# Power_Supply_TPS54260.net
KiCad netlist of a schematic drawn in Altium Designer
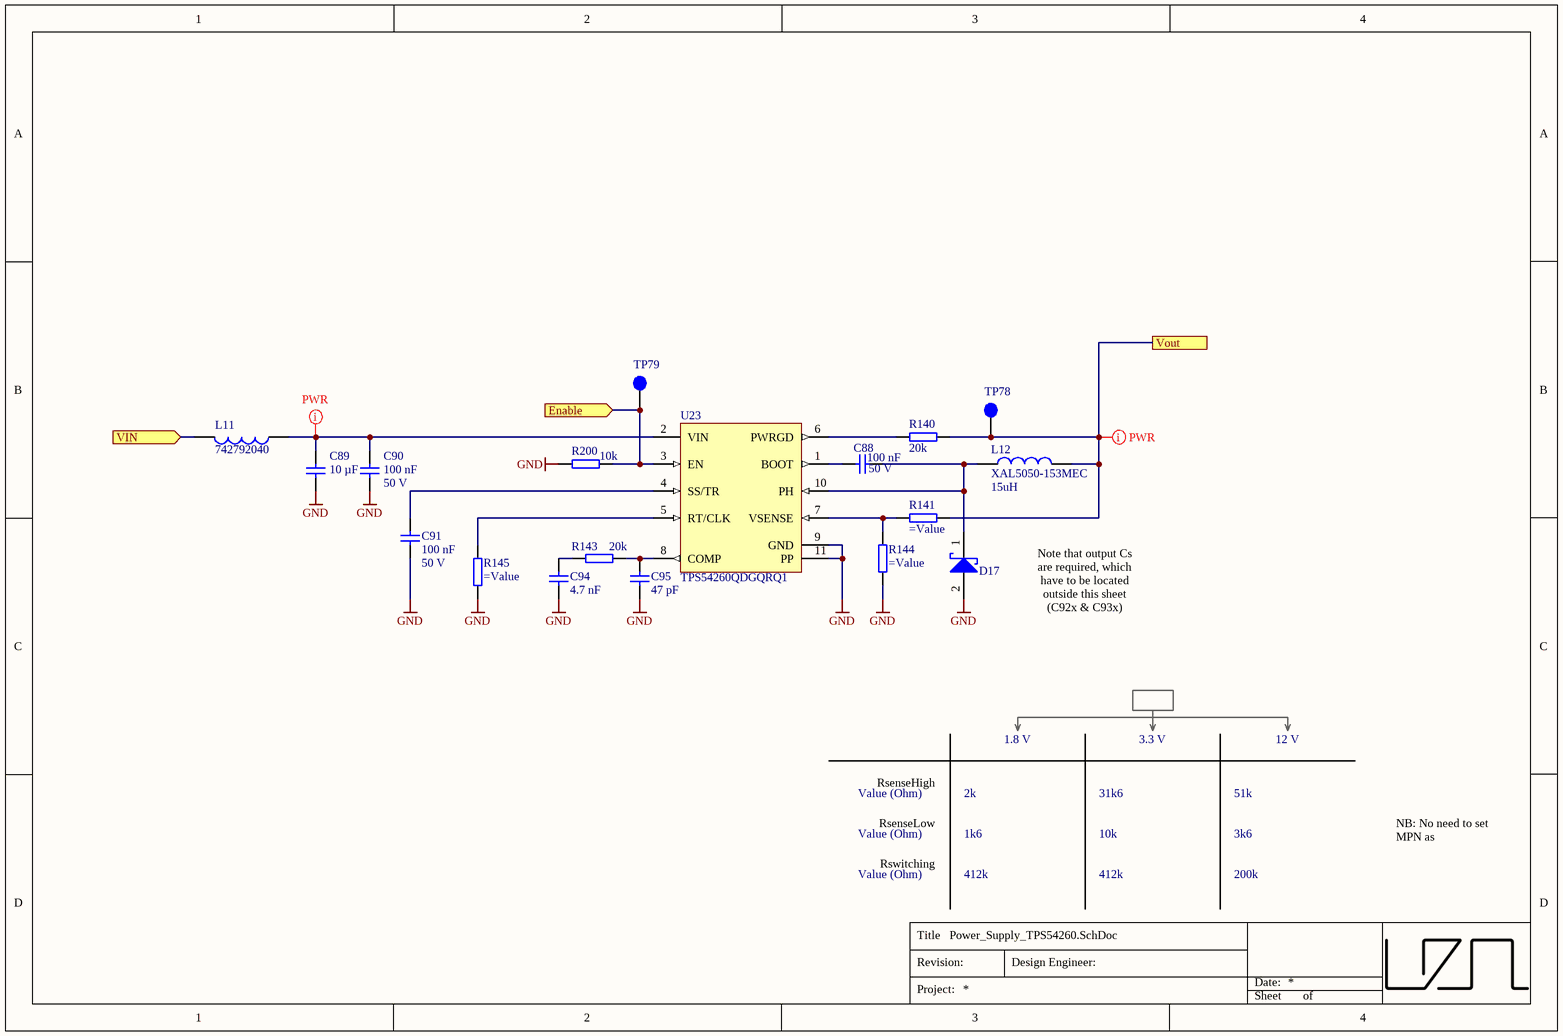
[diagram p0: Power_Supply_TPS54260.SchDoc]

(export (version "E")
  (design (tool "Eeschema 10.0.6"))
  (components
    (comp (ref "C88")
      (value "100 nF")
      (footprint "C_0603_TE")
      (description "Generic capacitor")
      (fields
        (field (name "TOLERANCE") "10 %")
        (field (name "VOLTAGE") "50 V")
        (field (name "MANUFACTURER PART NUMBER") "UZgen_C_0603_100nF_50V_X7R")
        (field (name "CREATED FROM") "AGeiger")
      )
      (libsource (lib "user") (part "CAP-NP"))
    )
    (comp (ref "C89")
      (value "10 µF")
      (footprint "C_1206_TE")
      (description "Generic capacitor")
      (fields
        (field (name "TOLERANCE") "10 %")
        (field (name "MANUFACTURER PART NUMBER") "UZgen_C_1206_10uF_50V_X7R")
        (field (name "CREATED FROM") "MGeier")
      )
      (libsource (lib "user") (part "CAP-NP"))
    )
    (comp (ref "C90")
      (value "100 nF")
      (footprint "C_0603_TE")
      (description "Generic capacitor")
      (fields
        (field (name "TOLERANCE") "10 %")
        (field (name "VOLTAGE") "50 V")
        (field (name "MANUFACTURER PART NUMBER") "UZgen_C_0603_100nF_50V_X7R")
        (field (name "CREATED FROM") "AGeiger")
      )
      (libsource (lib "user") (part "CAP-NP"))
    )
    (comp (ref "C91")
      (value "100 nF")
      (footprint "C_0603_TE")
      (description "Generic capacitor")
      (fields
        (field (name "TOLERANCE") "10 %")
        (field (name "VOLTAGE") "50 V")
        (field (name "MANUFACTURER PART NUMBER") "UZgen_C_0603_100nF_50V_X7R")
        (field (name "CREATED FROM") "AGeiger")
      )
      (libsource (lib "user") (part "CAP-NP"))
    )
    (comp (ref "C94")
      (value "4.7 nF")
      (footprint "C_0603_TE")
      (description "50V 4.7nF C0G ±5% 0603 Multilayer Ceramic Capacitors MLCC")
      (fields
        (field (name "TOLERANCE") "5%")
        (field (name "MANUFACTURER PART NUMBER") "GRM1885C1H472JA01D")
        (field (name "CREATED FROM") "MGeier")
      )
      (libsource (lib "user") (part "CAP-NP"))
    )
    (comp (ref "C95")
      (value "47 pF")
      (footprint "C_0603_TE")
      (description "50V 47pF C0G ±5% 0603 Multilayer Ceramic Capacitors MLCC")
      (fields
        (field (name "TOLERANCE") "5%")
        (field (name "MANUFACTURER PART NUMBER") "CL10C470JB8NNNC")
        (field (name "CREATED FROM") "MGeier")
      )
      (libsource (lib "user") (part "CAP-NP"))
    )
    (comp (ref "D17")
      (value "STPS340UY")
      (footprint "SMB")
      (description "Power Schottky Rectifier, 3 A, 40 V, 0.57 µF")
      (fields
        (field (name "MANUFACTURER") "STMicroelectronics")
        (field (name "LCSC PART NUMBER") "C283520")
        (field (name "CREATED FROM") "MGremer")
      )
      (libsource (lib "user") (part "STPS340-Y"))
    )
    (comp (ref "L11")
      (value "742792040")
      (footprint "WE-CBF_0805_High Current")
      (description "Inductance, 0805, 100 MHz, 600 Ohm, 2 A")
      (fields
        (field (name "MANUFACTURER") "Wuerth Elektronik")
        (field (name "LCSC PART NUMBER") "C2661857")
        (field (name "CREATED FROM") "AGeiger")
      )
      (libsource (lib "user") (part "WE-CBF"))
    )
    (comp (ref "L12")
      (value "XAL5050-153MEC")
      (footprint "XAL5050153MEC")
      (description "15uH@1MHz  ±20%, 3.9A, 76.7mOhm")
      (fields
        (field (name "ALTIUM_VALUE") "15uH")
        (field (name "MF") "EPCOS / TDK")
        (field (name "MPN") "B82464G4154M")
        (field (name "CREATED FROM") "FRosner")
      )
      (libsource (lib "user") (part "B82464G4154M"))
    )
    (comp (ref "R140")
      (value "20k")
      (footprint "R_0603_TE")
      (description "Generic resistor")
      (fields
        (field (name "TOLERANCE") "1 %")
        (field (name "MANUFACTURER PART NUMBER") "UZgen_R_0603_20k")
        (field (name "CREATED FROM") "UZgenTool")
      )
      (libsource (lib "user") (part "RES"))
    )
    (comp (ref "R141")
      (value "~")
      (footprint "R_0603_TE")
      (description "Generic resistor (parametric)")
      (fields
        (field (name "TOLERANCE") "1 %")
        (field (name "MANUFACTURER PART NUMBER") "UZgen_R_0603_")
        (field (name "CREATED FROM") "UZgenTool")
      )
      (libsource (lib "user") (part "RES"))
    )
    (comp (ref "R143")
      (value "20k")
      (footprint "R_0603_TE")
      (description "Generic resistor")
      (fields
        (field (name "TOLERANCE") "1 %")
        (field (name "MANUFACTURER PART NUMBER") "UZgen_R_0603_20k")
        (field (name "CREATED FROM") "UZgenTool")
      )
      (libsource (lib "user") (part "RES"))
    )
    (comp (ref "R144")
      (value "~")
      (footprint "R_0603_TE")
      (description "Generic resistor (parametric)")
      (fields
        (field (name "TOLERANCE") "1 %")
        (field (name "MANUFACTURER PART NUMBER") "UZgen_R_0603_")
        (field (name "CREATED FROM") "UZgenTool")
      )
      (libsource (lib "user") (part "RES"))
    )
    (comp (ref "R145")
      (value "~")
      (footprint "R_0603_TE")
      (description "Generic resistor (parametric)")
      (fields
        (field (name "MANUFACTURER PART NUMBER") "UZgen_R_0603_")
        (field (name "MANUFACTURER") "UZgen")
        (field (name "CREATED FROM") "UZgenTool")
      )
      (libsource (lib "user") (part "RES"))
    )
    (comp (ref "R200")
      (value "10k")
      (footprint "R_0603_TE")
      (description "Generic resistor")
      (fields
        (field (name "TOLERANCE") "1 %")
        (field (name "MANUFACTURER PART NUMBER") "UZgen_R_0603_10k")
        (field (name "CREATED FROM") "AGeiger")
      )
      (libsource (lib "user") (part "RES"))
    )
    (comp (ref "TP78")
      (value "Testpoint 1mm")
      (footprint "TP_1mm")
      (fields
        (field (name "MANUFACTURER PART NUMBER") "NULL")
        (field (name "CREATED") "2018_06_25_AGeiger")
        (field (name "CREATED FROM") "AGeiger")
      )
      (libsource (lib "user") (part "TP_1mm"))
    )
    (comp (ref "TP79")
      (value "Testpoint 1mm")
      (footprint "TP_1mm")
      (fields
        (field (name "MANUFACTURER PART NUMBER") "NULL")
        (field (name "CREATED") "2018_06_25_AGeiger")
        (field (name "CREATED FROM") "AGeiger")
      )
      (libsource (lib "user") (part "TP_1mm"))
    )
    (comp (ref "U23")
      (value "TPS54260QDGQRQ1")
      (footprint "TSOP-10_DGQ0010D_N")
      (description "High Efficiency Step-Down Converter, MSOP Package, 2.5 A, 3.5 - 60 V input, adjustable output")
      (fields
        (field (name "MANUFACTURER") "Texas Instruments")
        (field (name "LCSC PART NUMBER") "C181278")
        (field (name "CREATED FROM") "MGremer")
      )
      (libsource (lib "user") (part "TI-TPS54260-Q1"))
    )
  )
  (nets
    (net (code "1") (name "/Enable") (class "Default")
      (node (ref "R200") (pin "2") (pinfunction "2_2") (pintype "passive"))
      (node (ref "TP79") (pin "1") (pintype "passive"))
      (node (ref "U23") (pin "3") (pinfunction "EN_3") (pintype "input"))
    )
    (net (code "2") (name "/VIN") (class "Default")
      (node (ref "L11") (pin "2") (pinfunction "2_2") (pintype "passive"))
    )
    (net (code "3") (name "/Vout") (class "Default")
      (node (ref "L12") (pin "2") (pinfunction "2_2") (pintype "passive"))
      (node (ref "R140") (pin "1") (pinfunction "1_1") (pintype "passive"))
      (node (ref "R141") (pin "1") (pinfunction "1_1") (pintype "passive"))
      (node (ref "TP78") (pin "1") (pintype "passive"))
    )
    (net (code "4") (name "GND") (class "Default")
      (node (ref "C89") (pin "2") (pinfunction "2_2") (pintype "passive"))
      (node (ref "C90") (pin "1") (pinfunction "1_1") (pintype "passive"))
      (node (ref "C91") (pin "1") (pinfunction "1_1") (pintype "passive"))
      (node (ref "C94") (pin "2") (pinfunction "2_2") (pintype "passive"))
      (node (ref "C95") (pin "2") (pinfunction "2_2") (pintype "passive"))
      (node (ref "D17") (pin "2") (pinfunction "A_2") (pintype "passive"))
      (node (ref "R144") (pin "2") (pinfunction "2_2") (pintype "passive"))
      (node (ref "R145") (pin "2") (pinfunction "2_2") (pintype "passive"))
      (node (ref "R200") (pin "1") (pinfunction "1_1") (pintype "passive"))
      (node (ref "U23") (pin "11") (pinfunction "PP_11") (pintype "power_in"))
      (node (ref "U23") (pin "9") (pinfunction "GND_9") (pintype "power_in"))
    )
    (net (code "5") (name "Net-(C94-Pad1)") (class "Default")
      (node (ref "C94") (pin "1") (pinfunction "1_1") (pintype "passive"))
      (node (ref "R143") (pin "2") (pinfunction "2_2") (pintype "passive"))
    )
    (net (code "6") (name "Net-(D17-K)") (class "Default")
      (node (ref "C88") (pin "1") (pinfunction "1_1") (pintype "passive"))
      (node (ref "D17") (pin "1") (pinfunction "K_1") (pintype "passive"))
      (node (ref "L12") (pin "1") (pinfunction "1_1") (pintype "passive"))
      (node (ref "U23") (pin "10") (pinfunction "PH_10") (pintype "input"))
    )
    (net (code "7") (name "Net-(U23-BOOT)") (class "Default")
      (node (ref "C88") (pin "2") (pinfunction "2_2") (pintype "passive"))
      (node (ref "U23") (pin "1") (pinfunction "BOOT_1") (pintype "output"))
    )
    (net (code "8") (name "Net-(U23-COMP)") (class "Default")
      (node (ref "C95") (pin "1") (pinfunction "1_1") (pintype "passive"))
      (node (ref "R143") (pin "1") (pinfunction "1_1") (pintype "passive"))
      (node (ref "U23") (pin "8") (pinfunction "COMP_8") (pintype "output"))
    )
    (net (code "9") (name "Net-(U23-PWRGD)") (class "Default")
      (node (ref "R140") (pin "2") (pinfunction "2_2") (pintype "passive"))
      (node (ref "U23") (pin "6") (pinfunction "PWRGD_6") (pintype "output"))
    )
    (net (code "10") (name "Net-(U23-RT{slash}CLK)") (class "Default")
      (node (ref "R145") (pin "1") (pinfunction "1_1") (pintype "passive"))
      (node (ref "U23") (pin "5") (pinfunction "RT/CLK_5") (pintype "input"))
    )
    (net (code "11") (name "Net-(U23-SS{slash}TR)") (class "Default")
      (node (ref "C91") (pin "2") (pinfunction "2_2") (pintype "passive"))
      (node (ref "U23") (pin "4") (pinfunction "SS/TR_4") (pintype "input"))
    )
    (net (code "12") (name "Net-(U23-VIN)") (class "Default")
      (node (ref "C89") (pin "1") (pinfunction "1_1") (pintype "passive"))
      (node (ref "C90") (pin "2") (pinfunction "2_2") (pintype "passive"))
      (node (ref "L11") (pin "1") (pinfunction "1_1") (pintype "passive"))
      (node (ref "U23") (pin "2") (pinfunction "VIN_2") (pintype "power_in"))
    )
    (net (code "13") (name "Net-(U23-VSENSE)") (class "Default")
      (node (ref "R141") (pin "2") (pinfunction "2_2") (pintype "passive"))
      (node (ref "R144") (pin "1") (pinfunction "1_1") (pintype "passive"))
      (node (ref "U23") (pin "7") (pinfunction "VSENSE_7") (pintype "input"))
    )
  )
)
